# RFM2Pi_v2_6.net
KiCad netlist of a schematic drawn in EAGLE
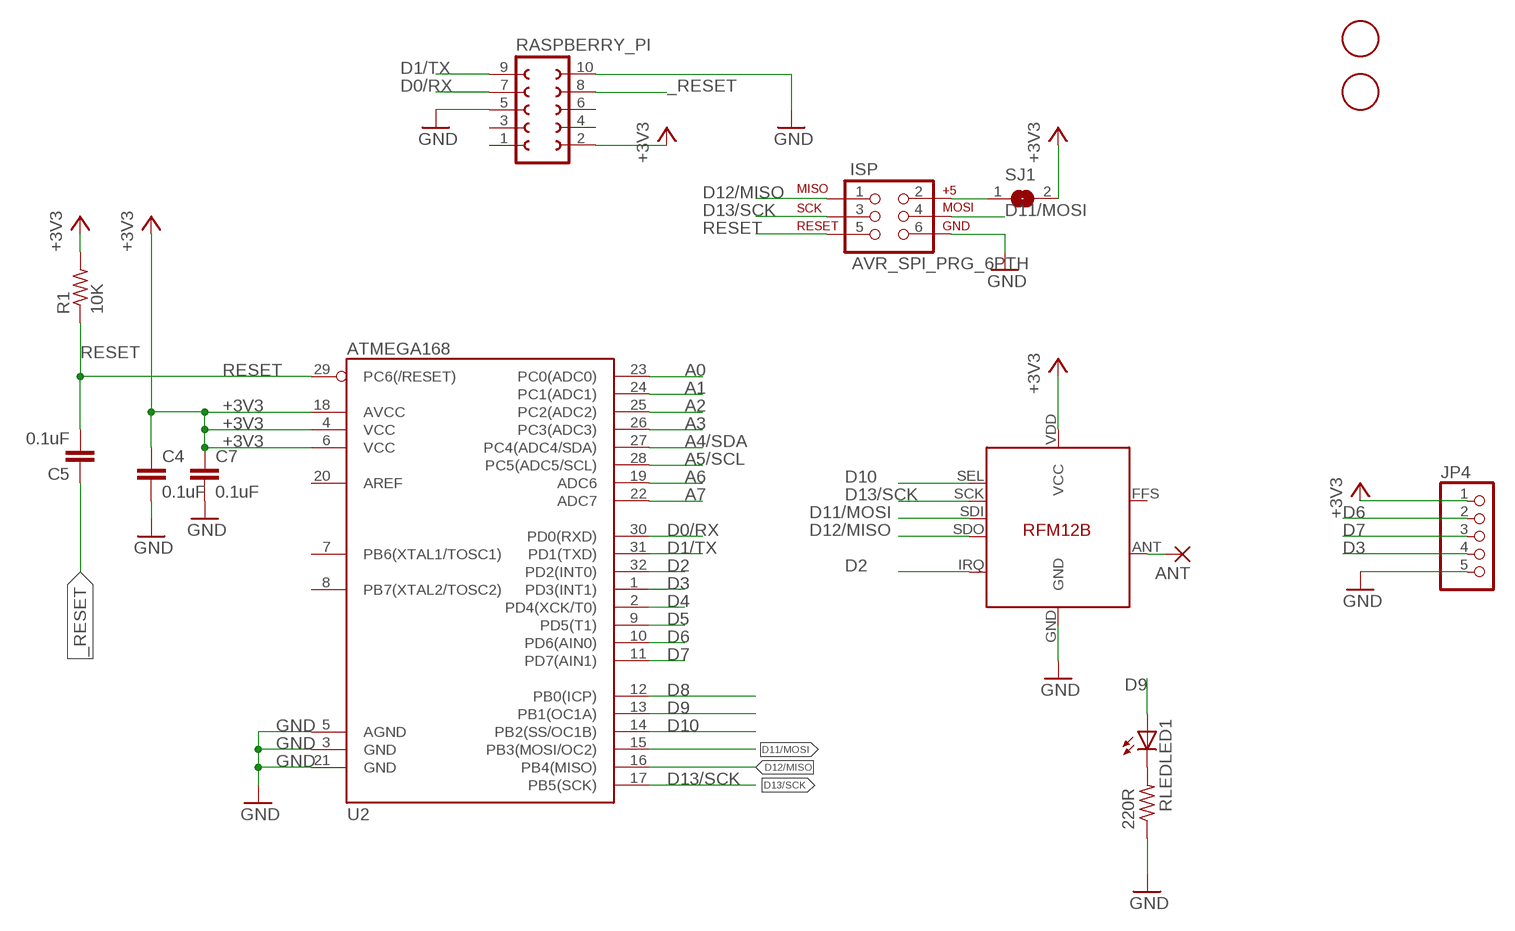
[diagram p0: schematic, sheet 1]

(export (version "E")
  (design (tool "Eeschema 10.0.6"))
  (components
    (comp (ref "ANT")
      (value "1,6/0,8")
      (footprint "eagle-import:1,6_0,8")
      (libsource (lib "eagle-import") (part "1,6/0,8"))
    )
    (comp (ref "C4")
      (value "0.1uF")
      (footprint "eagle-import:C0603")
      (libsource (lib "eagle-import") (part "C-EUC0603"))
    )
    (comp (ref "C5")
      (value "0.1uF")
      (footprint "eagle-import:C0603")
      (libsource (lib "eagle-import") (part "C-EUC0603"))
    )
    (comp (ref "C7")
      (value "0.1uF")
      (footprint "eagle-import:C0603")
      (libsource (lib "eagle-import") (part "resistor_C-EUC0603"))
    )
    (comp (ref "ISP")
      (value "AVR_SPI_PRG_6PTH")
      (footprint "eagle-import:2X3")
      (libsource (lib "eagle-import") (part "AVR_SPI_PRG_6PTH"))
    )
    (comp (ref "JP4")
      (value "PINHD-1X5")
      (footprint "eagle-import:1X05")
      (libsource (lib "eagle-import") (part "PINHD-1X5"))
    )
    (comp (ref "LED1")
      (value "LEDSML0603")
      (footprint "eagle-import:SML0603")
      (libsource (lib "eagle-import") (part "LEDSML0603"))
    )
    (comp (ref "R1")
      (value "10K")
      (footprint "eagle-import:R0603")
      (libsource (lib "eagle-import") (part "R-US_R0603"))
    )
    (comp (ref "RASPBERRY_PI")
      (value "FE05-2")
      (footprint "eagle-import:FE05-2")
      (libsource (lib "eagle-import") (part "FE05-2"))
    )
    (comp (ref "RFM12B")
      (value "RFM12B")
      (footprint "eagle-import:RFM12B")
      (libsource (lib "eagle-import") (part "RFM12B"))
    )
    (comp (ref "RLED")
      (value "220R")
      (footprint "eagle-import:R0603")
      (libsource (lib "eagle-import") (part "R-US_R0603"))
    )
    (comp (ref "SJ1") (value "SJ") (footprint "eagle-import:SJ") (libsource (lib "eagle-import") (part "SJ")))
    (comp (ref "U$1")
      (value "FIDUCIAL")
      (footprint "eagle-import:FIDUCIAL_1MM")
      (libsource (lib "eagle-import") (part "FIDUCIAL"))
    )
    (comp (ref "U$2")
      (value "FIDUCIAL")
      (footprint "eagle-import:FIDUCIAL_1MM")
      (libsource (lib "eagle-import") (part "FIDUCIAL"))
    )
    (comp (ref "U2")
      (value "ATMEGA168")
      (footprint "eagle-import:TQFP32-08")
      (libsource (lib "eagle-import") (part "ATMEGA168"))
    )
  )
  (nets
    (net (code "1") (name "+3V3") (class "Default")
      (node (ref "C4") (pin "1") (pinfunction "1_1") (pintype "passive"))
      (node (ref "C7") (pin "1") (pinfunction "1_1") (pintype "passive"))
      (node (ref "JP4") (pin "1") (pinfunction "1_1") (pintype "passive"))
      (node (ref "R1") (pin "2") (pinfunction "2_2") (pintype "passive"))
      (node (ref "RASPBERRY_PI") (pin "2") (pinfunction "2_2") (pintype "passive"))
      (node (ref "RFM12B") (pin "VDD") (pinfunction "VCC_VDD") (pintype "power_in"))
      (node (ref "SJ1") (pin "2") (pinfunction "2_2") (pintype "passive"))
      (node (ref "U2") (pin "18") (pinfunction "AVCC_18") (pintype "bidirectional"))
      (node (ref "U2") (pin "4") (pinfunction "VCC_4") (pintype "bidirectional"))
      (node (ref "U2") (pin "6") (pinfunction "VCC_6") (pintype "bidirectional"))
    )
    (net (code "2") (name "/A0") (class "Default")
      (node (ref "U2") (pin "23") (pinfunction "PC0(ADC0)_23") (pintype "bidirectional"))
    )
    (net (code "3") (name "/A1") (class "Default")
      (node (ref "U2") (pin "24") (pinfunction "PC1(ADC1)_24") (pintype "bidirectional"))
    )
    (net (code "4") (name "/A2") (class "Default")
      (node (ref "U2") (pin "25") (pinfunction "PC2(ADC2)_25") (pintype "bidirectional"))
    )
    (net (code "5") (name "/A3") (class "Default")
      (node (ref "U2") (pin "26") (pinfunction "PC3(ADC3)_26") (pintype "bidirectional"))
    )
    (net (code "6") (name "/A4{slash}SDA") (class "Default")
      (node (ref "U2") (pin "27") (pinfunction "PC4(ADC4/SDA)_27") (pintype "bidirectional"))
    )
    (net (code "7") (name "/A5{slash}SCL") (class "Default")
      (node (ref "U2") (pin "28") (pinfunction "PC5(ADC5/SCL)_28") (pintype "bidirectional"))
    )
    (net (code "8") (name "/A6") (class "Default")
      (node (ref "U2") (pin "19") (pinfunction "ADC6_19") (pintype "bidirectional"))
    )
    (net (code "9") (name "/A7") (class "Default")
      (node (ref "U2") (pin "22") (pinfunction "ADC7_22") (pintype "bidirectional"))
    )
    (net (code "10") (name "/D0{slash}RX") (class "Default")
      (node (ref "RASPBERRY_PI") (pin "7") (pinfunction "7_7") (pintype "passive"))
      (node (ref "U2") (pin "30") (pinfunction "PD0(RXD)_30") (pintype "bidirectional"))
    )
    (net (code "11") (name "/D1{slash}TX") (class "Default")
      (node (ref "RASPBERRY_PI") (pin "9") (pinfunction "9_9") (pintype "passive"))
      (node (ref "U2") (pin "31") (pinfunction "PD1(TXD)_31") (pintype "bidirectional"))
    )
    (net (code "12") (name "/D2") (class "Default")
      (node (ref "RFM12B") (pin "IRQ") (pinfunction "IRQ_IRQ") (pintype "open_collector"))
      (node (ref "U2") (pin "32") (pinfunction "PD2(INT0)_32") (pintype "bidirectional"))
    )
    (net (code "13") (name "/D3") (class "Default")
      (node (ref "JP4") (pin "4") (pinfunction "4_4") (pintype "passive"))
      (node (ref "U2") (pin "1") (pinfunction "PD3(INT1)_1") (pintype "bidirectional"))
    )
    (net (code "14") (name "/D4") (class "Default")
      (node (ref "U2") (pin "2") (pinfunction "PD4(XCK/T0)_2") (pintype "bidirectional"))
    )
    (net (code "15") (name "/D5") (class "Default")
      (node (ref "U2") (pin "9") (pinfunction "PD5(T1)_9") (pintype "bidirectional"))
    )
    (net (code "16") (name "/D6") (class "Default")
      (node (ref "JP4") (pin "2") (pinfunction "2_2") (pintype "passive"))
      (node (ref "U2") (pin "10") (pinfunction "PD6(AIN0)_10") (pintype "bidirectional"))
    )
    (net (code "17") (name "/D7") (class "Default")
      (node (ref "JP4") (pin "3") (pinfunction "3_3") (pintype "passive"))
      (node (ref "U2") (pin "11") (pinfunction "PD7(AIN1)_11") (pintype "bidirectional"))
    )
    (net (code "18") (name "/D8") (class "Default")
      (node (ref "U2") (pin "12") (pinfunction "PB0(ICP)_12") (pintype "bidirectional"))
    )
    (net (code "19") (name "/D9") (class "Default")
      (node (ref "LED1") (pin "A") (pinfunction "A_A") (pintype "passive"))
      (node (ref "U2") (pin "13") (pinfunction "PB1(OC1A)_13") (pintype "bidirectional"))
    )
    (net (code "20") (name "/D10") (class "Default")
      (node (ref "RFM12B") (pin "SEL") (pinfunction "SEL_SEL") (pintype "input"))
      (node (ref "U2") (pin "14") (pinfunction "PB2(SS/OC1B)_14") (pintype "bidirectional"))
    )
    (net (code "21") (name "/RESET") (class "Default")
      (node (ref "C5") (pin "2") (pinfunction "2_2") (pintype "passive"))
      (node (ref "ISP") (pin "5") (pinfunction "5_5") (pintype "passive"))
      (node (ref "R1") (pin "1") (pinfunction "1_1") (pintype "passive"))
      (node (ref "U2") (pin "29") (pinfunction "PC6(/RESET)_29") (pintype "bidirectional"))
    )
    (net (code "22") (name "D11{slash}MOSI") (class "Default")
      (node (ref "ISP") (pin "4") (pinfunction "4_4") (pintype "passive"))
      (node (ref "RFM12B") (pin "SDI") (pinfunction "SDI_SDI") (pintype "input"))
      (node (ref "U2") (pin "15") (pinfunction "PB3(MOSI/OC2)_15") (pintype "bidirectional"))
    )
    (net (code "23") (name "D12{slash}MISO") (class "Default")
      (node (ref "ISP") (pin "1") (pinfunction "1_1") (pintype "passive"))
      (node (ref "RFM12B") (pin "SDO") (pinfunction "SDO_SDO") (pintype "output"))
      (node (ref "U2") (pin "16") (pinfunction "PB4(MISO)_16") (pintype "bidirectional"))
    )
    (net (code "24") (name "D13{slash}SCK") (class "Default")
      (node (ref "ISP") (pin "3") (pinfunction "3_3") (pintype "passive"))
      (node (ref "RFM12B") (pin "SCK") (pinfunction "SCK_SCK") (pintype "input"))
      (node (ref "U2") (pin "17") (pinfunction "PB5(SCK)_17") (pintype "bidirectional"))
    )
    (net (code "25") (name "GND") (class "Default")
      (node (ref "C4") (pin "2") (pinfunction "2_2") (pintype "passive"))
      (node (ref "C7") (pin "2") (pinfunction "2_2") (pintype "passive"))
      (node (ref "ISP") (pin "6") (pinfunction "6_6") (pintype "passive"))
      (node (ref "JP4") (pin "5") (pinfunction "5_5") (pintype "passive"))
      (node (ref "RASPBERRY_PI") (pin "10") (pinfunction "10_10") (pintype "passive"))
      (node (ref "RASPBERRY_PI") (pin "5") (pinfunction "5_5") (pintype "passive"))
      (node (ref "RFM12B") (pin "GND") (pinfunction "GND_GND") (pintype "power_in"))
      (node (ref "RLED") (pin "1") (pinfunction "1_1") (pintype "passive"))
      (node (ref "U2") (pin "21") (pinfunction "GND_21") (pintype "bidirectional"))
      (node (ref "U2") (pin "3") (pinfunction "GND_3") (pintype "bidirectional"))
      (node (ref "U2") (pin "5") (pinfunction "AGND_5") (pintype "bidirectional"))
    )
    (net (code "26") (name "Net-(ANT-P)") (class "Default")
      (node (ref "ANT") (pin "1") (pinfunction "P_1") (pintype "passive"))
      (node (ref "RFM12B") (pin "ANT") (pinfunction "ANT_ANT") (pintype "passive"))
    )
    (net (code "27") (name "Net-(ISP-Pad2)") (class "Default")
      (node (ref "ISP") (pin "2") (pinfunction "2_2") (pintype "passive"))
      (node (ref "SJ1") (pin "1") (pinfunction "1_1") (pintype "passive"))
    )
    (net (code "28") (name "Net-(LED1-PadC)") (class "Default")
      (node (ref "LED1") (pin "C") (pinfunction "C_C") (pintype "passive"))
      (node (ref "RLED") (pin "2") (pinfunction "2_2") (pintype "passive"))
    )
    (net (code "29") (name "_RESET") (class "Default")
      (node (ref "C5") (pin "1") (pinfunction "1_1") (pintype "passive"))
      (node (ref "RASPBERRY_PI") (pin "8") (pinfunction "8_8") (pintype "passive"))
    )
    (net (code "30") (name "unconnected-(RASPBERRY_PI-Pad1)") (class "Default")
      (node (ref "RASPBERRY_PI") (pin "1") (pinfunction "1_1") (pintype "passive"))
    )
    (net (code "31") (name "unconnected-(RASPBERRY_PI-Pad3)") (class "Default")
      (node (ref "RASPBERRY_PI") (pin "3") (pinfunction "3_3") (pintype "passive"))
    )
    (net (code "32") (name "unconnected-(RASPBERRY_PI-Pad4)") (class "Default")
      (node (ref "RASPBERRY_PI") (pin "4") (pinfunction "4_4") (pintype "passive"))
    )
    (net (code "33") (name "unconnected-(RASPBERRY_PI-Pad6)") (class "Default")
      (node (ref "RASPBERRY_PI") (pin "6") (pinfunction "6_6") (pintype "passive"))
    )
    (net (code "34") (name "unconnected-(RFM12B-PadFFS)") (class "Default")
      (node (ref "RFM12B") (pin "FFS") (pinfunction "FFS_FFS") (pintype "bidirectional"))
    )
    (net (code "35") (name "unconnected-(U2-AREF-Pad20)") (class "Default")
      (node (ref "U2") (pin "20") (pinfunction "AREF_20") (pintype "bidirectional"))
    )
    (net (code "36") (name "unconnected-(U2-PB6(XTAL1{slash}TOSC1)-Pad7)") (class "Default")
      (node (ref "U2") (pin "7") (pinfunction "PB6(XTAL1/TOSC1)_7") (pintype "bidirectional"))
    )
    (net (code "37") (name "unconnected-(U2-PB7(XTAL2{slash}TOSC2)-Pad8)") (class "Default")
      (node (ref "U2") (pin "8") (pinfunction "PB7(XTAL2/TOSC2)_8") (pintype "bidirectional"))
    )
  )
)
